# RPi_Controller.net
KiCad netlist of a schematic drawn in EAGLE
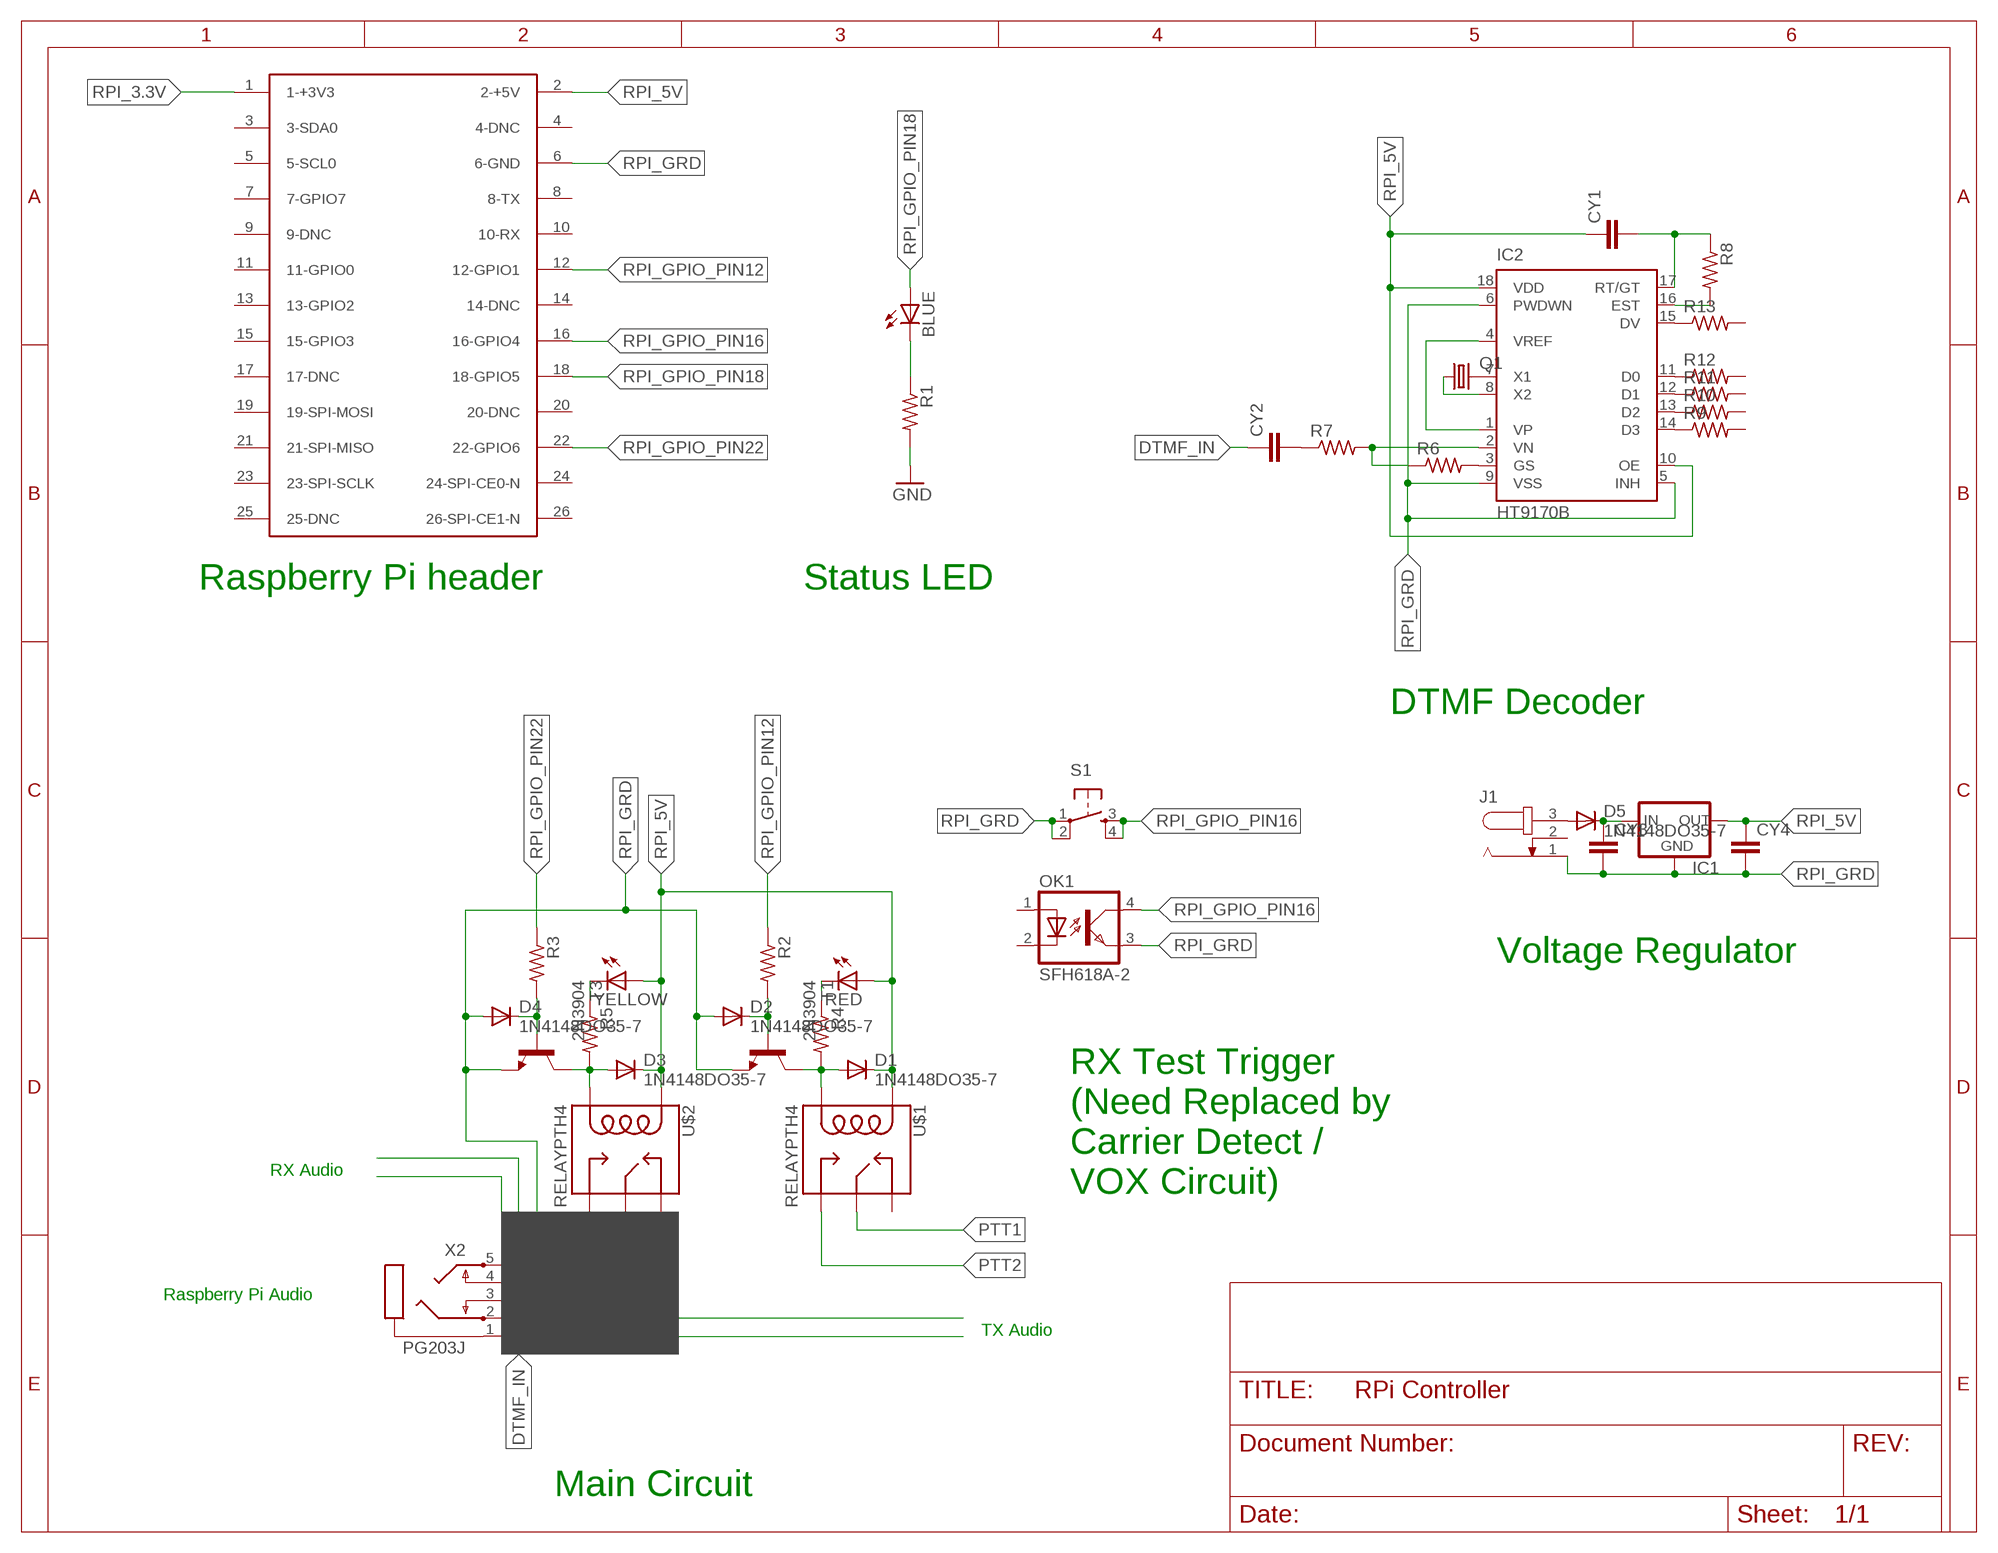
[diagram p0: schematic, sheet 1]

(export (version "E")
  (design (tool "Eeschema 10.0.6"))
  (components
    (comp (ref "BLUE")
      (value "LED3MM")
      (footprint "eagle-import:LED3MM")
      (libsource (lib "eagle-import") (part "LED3MM"))
    )
    (comp (ref "CY1")
      (value "CYYC7B5")
      (footprint "eagle-import:YC7B5")
      (libsource (lib "eagle-import") (part "CYYC7B5"))
    )
    (comp (ref "CY2")
      (value "CYYC7B5")
      (footprint "eagle-import:YC7B5")
      (libsource (lib "eagle-import") (part "CYYC7B5"))
    )
    (comp (ref "CY3")
      (value "CYYC7B5")
      (footprint "eagle-import:YC7B5")
      (libsource (lib "eagle-import") (part "CYYC7B5"))
    )
    (comp (ref "CY4")
      (value "CYYC7B5")
      (footprint "eagle-import:YC7B5")
      (libsource (lib "eagle-import") (part "CYYC7B5"))
    )
    (comp (ref "D1")
      (value "1N4148DO35-7")
      (footprint "eagle-import:DO35-7")
      (libsource (lib "eagle-import") (part "1N4148DO35-7"))
    )
    (comp (ref "D2")
      (value "1N4148DO35-7")
      (footprint "eagle-import:DO35-7")
      (libsource (lib "eagle-import") (part "1N4148DO35-7"))
    )
    (comp (ref "D3")
      (value "1N4148DO35-7")
      (footprint "eagle-import:DO35-7")
      (libsource (lib "eagle-import") (part "1N4148DO35-7"))
    )
    (comp (ref "D4")
      (value "1N4148DO35-7")
      (footprint "eagle-import:DO35-7")
      (libsource (lib "eagle-import") (part "1N4148DO35-7"))
    )
    (comp (ref "D5")
      (value "1N4148DO35-7")
      (footprint "eagle-import:DO35-7")
      (libsource (lib "eagle-import") (part "1N4148DO35-7"))
    )
    (comp (ref "IC1")
      (value "V_REG_78XX-TO-220")
      (footprint "eagle-import:TO-220-ALT")
      (libsource (lib "eagle-import") (part "V_REG_78XX-TO-220"))
    )
    (comp (ref "IC2")
      (value "HT9170B")
      (footprint "eagle-import:DIL18")
      (libsource (lib "eagle-import") (part "HT9170B"))
    )
    (comp (ref "J1")
      (value "JACK-PLUG0")
      (footprint "eagle-import:SPC4077")
      (libsource (lib "eagle-import") (part "JACK-PLUG0"))
    )
    (comp (ref "OK1")
      (value "SFH618A-2")
      (footprint "eagle-import:DIP4")
      (fields (field (name "MF") "VISHAY/TELEFUNKEN"))
      (libsource (lib "eagle-import") (part "SFH618?A-2"))
    )
    (comp (ref "Q1")
      (value "CRYSTALHC49U-V")
      (footprint "eagle-import:HC49U-V")
      (libsource (lib "eagle-import") (part "CRYSTALHC49U-V"))
    )
    (comp (ref "R1")
      (value "R-US_0204/7")
      (footprint "eagle-import:0204_7")
      (libsource (lib "eagle-import") (part "R-US_0204/7"))
    )
    (comp (ref "R2")
      (value "R-US_0204/7")
      (footprint "eagle-import:0204_7")
      (libsource (lib "eagle-import") (part "R-US_0204/7"))
    )
    (comp (ref "R3")
      (value "R-US_0204/7")
      (footprint "eagle-import:0204_7")
      (libsource (lib "eagle-import") (part "R-US_0204/7"))
    )
    (comp (ref "R4")
      (value "R-US_0204/7")
      (footprint "eagle-import:0204_7")
      (libsource (lib "eagle-import") (part "R-US_0204/7"))
    )
    (comp (ref "R5")
      (value "R-US_0204/7")
      (footprint "eagle-import:0204_7")
      (libsource (lib "eagle-import") (part "R-US_0204/7"))
    )
    (comp (ref "R6")
      (value "R-US_0204/7")
      (footprint "eagle-import:0204_7")
      (libsource (lib "eagle-import") (part "R-US_0204/7"))
    )
    (comp (ref "R7")
      (value "R-US_0204/7")
      (footprint "eagle-import:0204_7")
      (libsource (lib "eagle-import") (part "R-US_0204/7"))
    )
    (comp (ref "R8")
      (value "R-US_0204/7")
      (footprint "eagle-import:0204_7")
      (libsource (lib "eagle-import") (part "R-US_0204/7"))
    )
    (comp (ref "R9")
      (value "R-US_0204/7")
      (footprint "eagle-import:0204_7")
      (libsource (lib "eagle-import") (part "R-US_0204/7"))
    )
    (comp (ref "R10")
      (value "R-US_0204/7")
      (footprint "eagle-import:0204_7")
      (libsource (lib "eagle-import") (part "R-US_0204/7"))
    )
    (comp (ref "R11")
      (value "R-US_0204/7")
      (footprint "eagle-import:0204_7")
      (libsource (lib "eagle-import") (part "R-US_0204/7"))
    )
    (comp (ref "R12")
      (value "R-US_0204/7")
      (footprint "eagle-import:0204_7")
      (libsource (lib "eagle-import") (part "R-US_0204/7"))
    )
    (comp (ref "R13")
      (value "R-US_0204/7")
      (footprint "eagle-import:0204_7")
      (libsource (lib "eagle-import") (part "R-US_0204/7"))
    )
    (comp (ref "RED")
      (value "LED3MM")
      (footprint "eagle-import:LED3MM")
      (libsource (lib "eagle-import") (part "LED3MM"))
    )
    (comp (ref "S1")
      (value "TAC_SWITCHPTH")
      (footprint "eagle-import:TACTILE-PTH")
      (libsource (lib "eagle-import") (part "TAC_SWITCHPTH"))
    )
    (comp (ref "T1")
      (value "2N3904")
      (footprint "eagle-import:TO92")
      (libsource (lib "eagle-import") (part "2N3904"))
    )
    (comp (ref "T3")
      (value "2N3904")
      (footprint "eagle-import:TO92")
      (libsource (lib "eagle-import") (part "2N3904"))
    )
    (comp (ref "U$1")
      (value "RELAYPTH4")
      (footprint "eagle-import:RELAY-JZC")
      (libsource (lib "eagle-import") (part "RELAYPTH4"))
    )
    (comp (ref "U$2")
      (value "RELAYPTH4")
      (footprint "eagle-import:RELAY-JZC")
      (libsource (lib "eagle-import") (part "RELAYPTH4"))
    )
    (comp (ref "X1")
      (value "P1A")
      (footprint "eagle-import:RASPBERRY-PI-HEADER")
      (libsource (lib "eagle-import") (part "RASPBERRY-PIHEADER"))
    )
    (comp (ref "X2")
      (value "PG203J")
      (footprint "eagle-import:PG203J")
      (libsource (lib "eagle-import") (part "PG203J"))
    )
    (comp (ref "YELLOW")
      (value "LED3MM")
      (footprint "eagle-import:LED3MM")
      (libsource (lib "eagle-import") (part "LED3MM"))
    )
  )
  (nets
    (net (code "1") (name "DTMF_IN") (class "Default")
      (node (ref "CY2") (pin "1") (pinfunction "1_1") (pintype "passive"))
      (node (ref "U$2") (pin "4") (pinfunction "MAIN_4") (pintype "bidirectional"))
    )
    (net (code "2") (name "GND") (class "Default")
      (node (ref "R1") (pin "2") (pinfunction "2_2") (pintype "passive"))
    )
    (net (code "3") (name "Net-(BLUE-C)") (class "Default")
      (node (ref "BLUE") (pin "K") (pinfunction "C_K") (pintype "passive"))
      (node (ref "R1") (pin "1") (pinfunction "1_1") (pintype "passive"))
    )
    (net (code "4") (name "Net-(CY2-Pad2)") (class "Default")
      (node (ref "CY2") (pin "2") (pinfunction "2_2") (pintype "passive"))
      (node (ref "R7") (pin "1") (pinfunction "1_1") (pintype "passive"))
    )
    (net (code "5") (name "Net-(CY3-Pad1)") (class "Default")
      (node (ref "CY3") (pin "1") (pinfunction "1_1") (pintype "passive"))
      (node (ref "D5") (pin "C") (pinfunction "C_C") (pintype "passive"))
      (node (ref "IC1") (pin "IN") (pinfunction "IN_IN") (pintype "input"))
    )
    (net (code "6") (name "Net-(D5-PadA)") (class "Default")
      (node (ref "D5") (pin "A") (pinfunction "A_A") (pintype "passive"))
      (node (ref "J1") (pin "3") (pinfunction "3_3") (pintype "passive"))
    )
    (net (code "7") (name "Net-(IC2-D0)") (class "Default")
      (node (ref "IC2") (pin "11") (pinfunction "D0_11") (pintype "output"))
      (node (ref "R12") (pin "1") (pinfunction "1_1") (pintype "passive"))
    )
    (net (code "8") (name "Net-(IC2-D1)") (class "Default")
      (node (ref "IC2") (pin "12") (pinfunction "D1_12") (pintype "output"))
      (node (ref "R11") (pin "1") (pinfunction "1_1") (pintype "passive"))
    )
    (net (code "9") (name "Net-(IC2-D2)") (class "Default")
      (node (ref "IC2") (pin "13") (pinfunction "D2_13") (pintype "output"))
      (node (ref "R10") (pin "1") (pinfunction "1_1") (pintype "passive"))
    )
    (net (code "10") (name "Net-(IC2-D3)") (class "Default")
      (node (ref "IC2") (pin "14") (pinfunction "D3_14") (pintype "output"))
      (node (ref "R9") (pin "1") (pinfunction "1_1") (pintype "passive"))
    )
    (net (code "11") (name "Net-(IC2-DV)") (class "Default")
      (node (ref "IC2") (pin "15") (pinfunction "DV_15") (pintype "output"))
      (node (ref "R13") (pin "1") (pinfunction "1_1") (pintype "passive"))
    )
    (net (code "12") (name "Net-(IC2-EST)") (class "Default")
      (node (ref "IC2") (pin "16") (pinfunction "EST_16") (pintype "output"))
      (node (ref "R8") (pin "2") (pinfunction "2_2") (pintype "passive"))
    )
    (net (code "13") (name "Net-(IC2-GS)") (class "Default")
      (node (ref "IC2") (pin "3") (pinfunction "GS_3") (pintype "passive"))
      (node (ref "R6") (pin "2") (pinfunction "2_2") (pintype "passive"))
    )
    (net (code "14") (name "Net-(IC2-RT{slash}GT)") (class "Default")
      (node (ref "CY1") (pin "2") (pinfunction "2_2") (pintype "passive"))
      (node (ref "IC2") (pin "17") (pinfunction "RT/GT_17") (pintype "bidirectional"))
      (node (ref "R8") (pin "1") (pinfunction "1_1") (pintype "passive"))
    )
    (net (code "15") (name "Net-(IC2-VN)") (class "Default")
      (node (ref "IC2") (pin "2") (pinfunction "VN_2") (pintype "input"))
      (node (ref "R6") (pin "1") (pinfunction "1_1") (pintype "passive"))
      (node (ref "R7") (pin "2") (pinfunction "2_2") (pintype "passive"))
    )
    (net (code "16") (name "Net-(IC2-VP)") (class "Default")
      (node (ref "IC2") (pin "1") (pinfunction "VP_1") (pintype "input"))
      (node (ref "IC2") (pin "4") (pinfunction "VREF_4") (pintype "output"))
    )
    (net (code "17") (name "Net-(IC2-X1)") (class "Default")
      (node (ref "IC2") (pin "7") (pinfunction "X1_7") (pintype "input"))
      (node (ref "Q1") (pin "2") (pinfunction "2_2") (pintype "passive"))
    )
    (net (code "18") (name "Net-(IC2-X2)") (class "Default")
      (node (ref "IC2") (pin "8") (pinfunction "X2_8") (pintype "output"))
      (node (ref "Q1") (pin "1") (pinfunction "1_1") (pintype "passive"))
    )
    (net (code "19") (name "Net-(RED-C)") (class "Default")
      (node (ref "R4") (pin "1") (pinfunction "1_1") (pintype "passive"))
      (node (ref "RED") (pin "K") (pinfunction "C_K") (pintype "passive"))
    )
    (net (code "20") (name "Net-(T1-B)") (class "Default")
      (node (ref "D2") (pin "C") (pinfunction "C_C") (pintype "passive"))
      (node (ref "R2") (pin "2") (pinfunction "2_2") (pintype "passive"))
      (node (ref "T1") (pin "2") (pinfunction "B_2") (pintype "passive"))
    )
    (net (code "21") (name "Net-(T1-C)") (class "Default")
      (node (ref "D1") (pin "A") (pinfunction "A_A") (pintype "passive"))
      (node (ref "R4") (pin "2") (pinfunction "2_2") (pintype "passive"))
      (node (ref "T1") (pin "1") (pinfunction "C_1") (pintype "passive"))
      (node (ref "U$1") (pin "1") (pinfunction "COIL2_1") (pintype "bidirectional"))
    )
    (net (code "22") (name "Net-(T3-B)") (class "Default")
      (node (ref "D4") (pin "C") (pinfunction "C_C") (pintype "passive"))
      (node (ref "R3") (pin "2") (pinfunction "2_2") (pintype "passive"))
      (node (ref "T3") (pin "2") (pinfunction "B_2") (pintype "passive"))
    )
    (net (code "23") (name "Net-(T3-C)") (class "Default")
      (node (ref "D3") (pin "A") (pinfunction "A_A") (pintype "passive"))
      (node (ref "R5") (pin "2") (pinfunction "2_2") (pintype "passive"))
      (node (ref "T3") (pin "1") (pinfunction "C_1") (pintype "passive"))
      (node (ref "U$2") (pin "1") (pinfunction "COIL2_1") (pintype "bidirectional"))
    )
    (net (code "24") (name "Net-(U$2-NC)") (class "Default")
      (node (ref "U$2") (pin "2") (pinfunction "NC_2") (pintype "bidirectional"))
      (node (ref "X2") (pin "5") (pinfunction "5_5") (pintype "passive"))
    )
    (net (code "25") (name "Net-(YELLOW-C)") (class "Default")
      (node (ref "R5") (pin "1") (pinfunction "1_1") (pintype "passive"))
      (node (ref "YELLOW") (pin "K") (pinfunction "C_K") (pintype "passive"))
    )
    (net (code "26") (name "PTT1") (class "Default")
      (node (ref "U$1") (pin "4") (pinfunction "MAIN_4") (pintype "bidirectional"))
    )
    (net (code "27") (name "PTT2") (class "Default")
      (node (ref "U$1") (pin "3") (pinfunction "NO_3") (pintype "bidirectional"))
    )
    (net (code "28") (name "RPI_3.3V") (class "Default")
      (node (ref "X1") (pin "1") (pinfunction "1-+3V3_1") (pintype "bidirectional"))
    )
    (net (code "29") (name "RPI_5V") (class "Default")
      (node (ref "CY1") (pin "1") (pinfunction "1_1") (pintype "passive"))
      (node (ref "CY4") (pin "1") (pinfunction "1_1") (pintype "passive"))
      (node (ref "D1") (pin "C") (pinfunction "C_C") (pintype "passive"))
      (node (ref "D3") (pin "C") (pinfunction "C_C") (pintype "passive"))
      (node (ref "IC1") (pin "OUT") (pinfunction "OUT_OUT") (pintype "output"))
      (node (ref "IC2") (pin "10") (pinfunction "OE_10") (pintype "input"))
      (node (ref "IC2") (pin "18") (pinfunction "VDD_18") (pintype "power_in"))
      (node (ref "RED") (pin "A") (pinfunction "A_A") (pintype "passive"))
      (node (ref "U$1") (pin "5") (pinfunction "COIL1_5") (pintype "bidirectional"))
      (node (ref "U$2") (pin "5") (pinfunction "COIL1_5") (pintype "bidirectional"))
      (node (ref "X1") (pin "2") (pinfunction "2-+5V_2") (pintype "bidirectional"))
      (node (ref "YELLOW") (pin "A") (pinfunction "A_A") (pintype "passive"))
    )
    (net (code "30") (name "RPI_GPIO_PIN12") (class "Default")
      (node (ref "R2") (pin "1") (pinfunction "1_1") (pintype "passive"))
      (node (ref "X1") (pin "12") (pinfunction "12-GPIO1_12") (pintype "bidirectional"))
    )
    (net (code "31") (name "RPI_GPIO_PIN16") (class "Default")
      (node (ref "OK1") (pin "4") (pinfunction "COL_4") (pintype "passive"))
      (node (ref "S1") (pin "3") (pinfunction "3_3") (pintype "passive"))
      (node (ref "S1") (pin "4") (pinfunction "4_4") (pintype "passive"))
      (node (ref "X1") (pin "16") (pinfunction "16-GPIO4_16") (pintype "bidirectional"))
    )
    (net (code "32") (name "RPI_GPIO_PIN18") (class "Default")
      (node (ref "BLUE") (pin "A") (pinfunction "A_A") (pintype "passive"))
      (node (ref "X1") (pin "18") (pinfunction "18-GPIO5_18") (pintype "bidirectional"))
    )
    (net (code "33") (name "RPI_GPIO_PIN22") (class "Default")
      (node (ref "R3") (pin "1") (pinfunction "1_1") (pintype "passive"))
      (node (ref "X1") (pin "22") (pinfunction "22-GPIO6_22") (pintype "bidirectional"))
    )
    (net (code "34") (name "RPI_GRD") (class "Default")
      (node (ref "CY3") (pin "2") (pinfunction "2_2") (pintype "passive"))
      (node (ref "CY4") (pin "2") (pinfunction "2_2") (pintype "passive"))
      (node (ref "D2") (pin "A") (pinfunction "A_A") (pintype "passive"))
      (node (ref "D4") (pin "A") (pinfunction "A_A") (pintype "passive"))
      (node (ref "IC1") (pin "GND") (pinfunction "GND_GND") (pintype "input"))
      (node (ref "IC2") (pin "5") (pinfunction "INH_5") (pintype "input"))
      (node (ref "IC2") (pin "6") (pinfunction "PWDWN_6") (pintype "input"))
      (node (ref "IC2") (pin "9") (pinfunction "VSS_9") (pintype "power_in"))
      (node (ref "J1") (pin "1") (pinfunction "1_1") (pintype "passive"))
      (node (ref "OK1") (pin "3") (pinfunction "EMIT_3") (pintype "passive"))
      (node (ref "S1") (pin "1") (pinfunction "1_1") (pintype "passive"))
      (node (ref "S1") (pin "2") (pinfunction "2_2") (pintype "passive"))
      (node (ref "T1") (pin "3") (pinfunction "E_3") (pintype "passive"))
      (node (ref "T3") (pin "3") (pinfunction "E_3") (pintype "passive"))
      (node (ref "X1") (pin "6") (pinfunction "6-GND_6") (pintype "bidirectional"))
      (node (ref "X2") (pin "1") (pinfunction "1_1") (pintype "passive"))
    )
    (net (code "35") (name "unconnected-(J1-Pad2)") (class "Default")
      (node (ref "J1") (pin "2") (pinfunction "2_2") (pintype "passive"))
    )
    (net (code "36") (name "unconnected-(OK1-A-Pad1)") (class "Default")
      (node (ref "OK1") (pin "1") (pinfunction "A_1") (pintype "passive"))
    )
    (net (code "37") (name "unconnected-(OK1-C-Pad2)") (class "Default")
      (node (ref "OK1") (pin "2") (pinfunction "C_2") (pintype "passive"))
    )
    (net (code "38") (name "unconnected-(R9-Pad2)") (class "Default")
      (node (ref "R9") (pin "2") (pinfunction "2_2") (pintype "passive"))
    )
    (net (code "39") (name "unconnected-(R10-Pad2)") (class "Default")
      (node (ref "R10") (pin "2") (pinfunction "2_2") (pintype "passive"))
    )
    (net (code "40") (name "unconnected-(R11-Pad2)") (class "Default")
      (node (ref "R11") (pin "2") (pinfunction "2_2") (pintype "passive"))
    )
    (net (code "41") (name "unconnected-(R12-Pad2)") (class "Default")
      (node (ref "R12") (pin "2") (pinfunction "2_2") (pintype "passive"))
    )
    (net (code "42") (name "unconnected-(R13-Pad2)") (class "Default")
      (node (ref "R13") (pin "2") (pinfunction "2_2") (pintype "passive"))
    )
    (net (code "43") (name "unconnected-(U$1-NC-Pad2)") (class "Default")
      (node (ref "U$1") (pin "2") (pinfunction "NC_2") (pintype "bidirectional"))
    )
    (net (code "44") (name "unconnected-(U$2-NO-Pad3)") (class "Default")
      (node (ref "U$2") (pin "3") (pinfunction "NO_3") (pintype "bidirectional"))
    )
    (net (code "45") (name "unconnected-(X1-3-SDA0-Pad3)") (class "Default")
      (node (ref "X1") (pin "3") (pinfunction "3-SDA0_3") (pintype "bidirectional"))
    )
    (net (code "46") (name "unconnected-(X1-4-DNC-Pad4)") (class "Default")
      (node (ref "X1") (pin "4") (pinfunction "4-DNC_4") (pintype "bidirectional"))
    )
    (net (code "47") (name "unconnected-(X1-5-SCL0-Pad5)") (class "Default")
      (node (ref "X1") (pin "5") (pinfunction "5-SCL0_5") (pintype "bidirectional"))
    )
    (net (code "48") (name "unconnected-(X1-7-GPIO7-Pad7)") (class "Default")
      (node (ref "X1") (pin "7") (pinfunction "7-GPIO7_7") (pintype "bidirectional"))
    )
    (net (code "49") (name "unconnected-(X1-8-TX-Pad8)") (class "Default")
      (node (ref "X1") (pin "8") (pinfunction "8-TX_8") (pintype "bidirectional"))
    )
    (net (code "50") (name "unconnected-(X1-9-DNC-Pad9)") (class "Default")
      (node (ref "X1") (pin "9") (pinfunction "9-DNC_9") (pintype "bidirectional"))
    )
    (net (code "51") (name "unconnected-(X1-10-RX-Pad10)") (class "Default")
      (node (ref "X1") (pin "10") (pinfunction "10-RX_10") (pintype "bidirectional"))
    )
    (net (code "52") (name "unconnected-(X1-11-GPIO0-Pad11)") (class "Default")
      (node (ref "X1") (pin "11") (pinfunction "11-GPIO0_11") (pintype "bidirectional"))
    )
    (net (code "53") (name "unconnected-(X1-13-GPIO2-Pad13)") (class "Default")
      (node (ref "X1") (pin "13") (pinfunction "13-GPIO2_13") (pintype "bidirectional"))
    )
    (net (code "54") (name "unconnected-(X1-14-DNC-Pad14)") (class "Default")
      (node (ref "X1") (pin "14") (pinfunction "14-DNC_14") (pintype "bidirectional"))
    )
    (net (code "55") (name "unconnected-(X1-15-GPIO3-Pad15)") (class "Default")
      (node (ref "X1") (pin "15") (pinfunction "15-GPIO3_15") (pintype "bidirectional"))
    )
    (net (code "56") (name "unconnected-(X1-17-DNC-Pad17)") (class "Default")
      (node (ref "X1") (pin "17") (pinfunction "17-DNC_17") (pintype "bidirectional"))
    )
    (net (code "57") (name "unconnected-(X1-19-SPI-MOSI-Pad19)") (class "Default")
      (node (ref "X1") (pin "19") (pinfunction "19-SPI-MOSI_19") (pintype "bidirectional"))
    )
    (net (code "58") (name "unconnected-(X1-20-DNC-Pad20)") (class "Default")
      (node (ref "X1") (pin "20") (pinfunction "20-DNC_20") (pintype "bidirectional"))
    )
    (net (code "59") (name "unconnected-(X1-21-SPI-MISO-Pad21)") (class "Default")
      (node (ref "X1") (pin "21") (pinfunction "21-SPI-MISO_21") (pintype "bidirectional"))
    )
    (net (code "60") (name "unconnected-(X1-23-SPI-SCLK-Pad23)") (class "Default")
      (node (ref "X1") (pin "23") (pinfunction "23-SPI-SCLK_23") (pintype "bidirectional"))
    )
    (net (code "61") (name "unconnected-(X1-24-SPI-CE0-N-Pad24)") (class "Default")
      (node (ref "X1") (pin "24") (pinfunction "24-SPI-CE0-N_24") (pintype "bidirectional"))
    )
    (net (code "62") (name "unconnected-(X1-25-DNC-Pad25)") (class "Default")
      (node (ref "X1") (pin "25") (pinfunction "25-DNC_25") (pintype "bidirectional"))
    )
    (net (code "63") (name "unconnected-(X1-26-SPI-CE1-N-Pad26)") (class "Default")
      (node (ref "X1") (pin "26") (pinfunction "26-SPI-CE1-N_26") (pintype "bidirectional"))
    )
    (net (code "64") (name "unconnected-(X2-Pad2)") (class "Default")
      (node (ref "X2") (pin "2") (pinfunction "2_2") (pintype "passive"))
    )
    (net (code "65") (name "unconnected-(X2-Pad3)") (class "Default")
      (node (ref "X2") (pin "3") (pinfunction "3_3") (pintype "passive"))
    )
    (net (code "66") (name "unconnected-(X2-Pad4)") (class "Default")
      (node (ref "X2") (pin "4") (pinfunction "4_4") (pintype "passive"))
    )
  )
)
